# OLED_Display.net
KiCad netlist of a schematic drawn in EAGLE
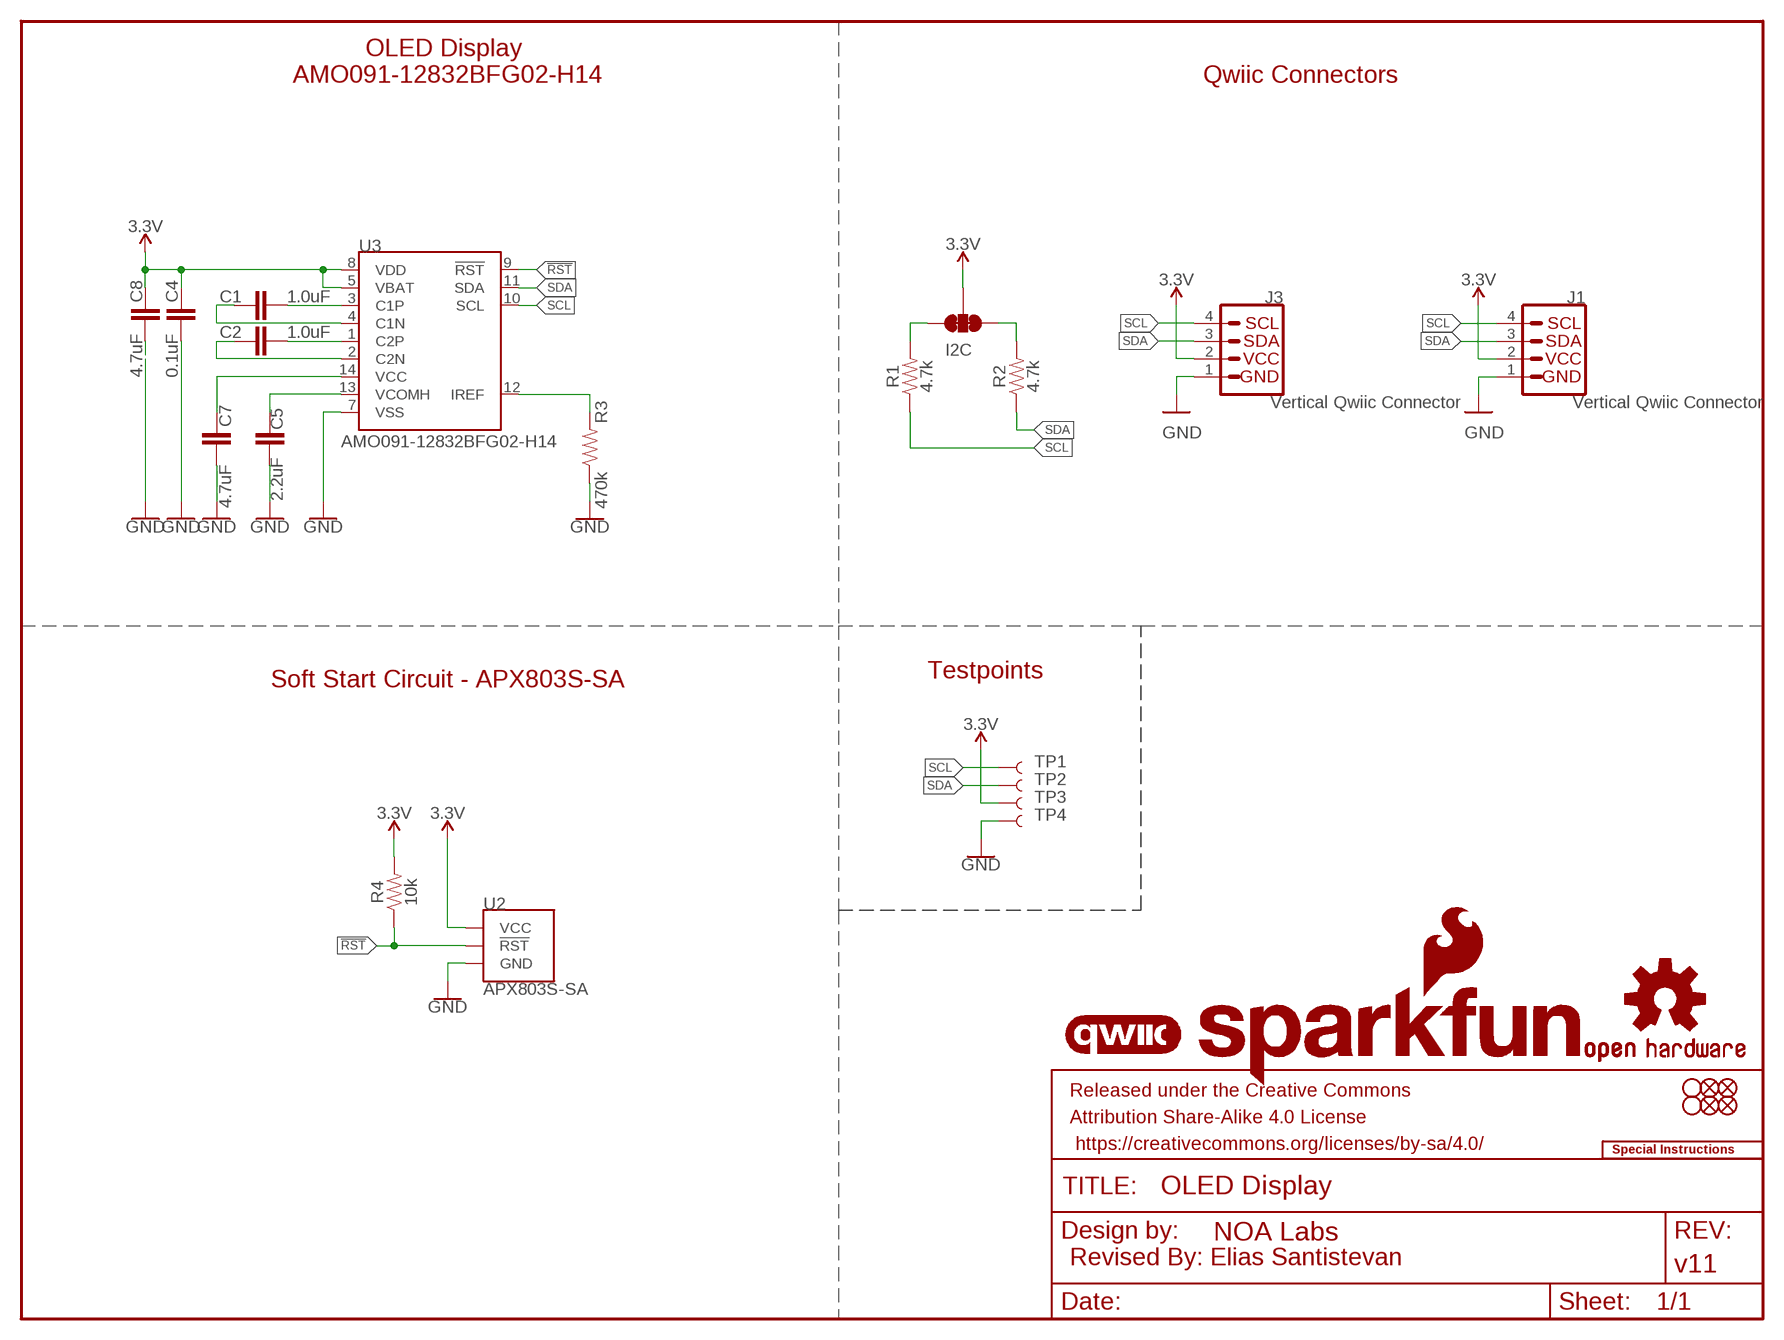
[diagram p0: schematic, sheet 1]

(export (version "E")
  (design (tool "Eeschema 10.0.6"))
  (components
    (comp (ref "C1")
      (value "1.0uF")
      (footprint "eagle-import:0603")
      (libsource (lib "eagle-import") (part "1.0UF-0603-16V-10%"))
    )
    (comp (ref "C2")
      (value "1.0uF")
      (footprint "eagle-import:0603")
      (libsource (lib "eagle-import") (part "1.0UF-0603-16V-10%"))
    )
    (comp (ref "C4")
      (value "0.1uF")
      (footprint "eagle-import:0603")
      (libsource (lib "eagle-import") (part "0.1UF-0603-25V-(+80/-20%)"))
    )
    (comp (ref "C5")
      (value "2.2uF")
      (footprint "eagle-import:0603")
      (libsource (lib "eagle-import") (part "2.2UF-0603-10V-20%"))
    )
    (comp (ref "C7")
      (value "4.7uF")
      (footprint "eagle-import:0603")
      (libsource (lib "eagle-import") (part "4.7UF-0603-6.3V-(10%)"))
    )
    (comp (ref "C8")
      (value "4.7uF")
      (footprint "eagle-import:0603")
      (libsource (lib "eagle-import") (part "4.7UF-0603-6.3V-(10%)"))
    )
    (comp (ref "FD1")
      (value "FIDUCIAL1X2")
      (footprint "eagle-import:FIDUCIAL-1X2")
      (libsource (lib "eagle-import") (part "FIDUCIAL1X2"))
    )
    (comp (ref "FD2")
      (value "FIDUCIAL1X2")
      (footprint "eagle-import:FIDUCIAL-1X2")
      (libsource (lib "eagle-import") (part "FIDUCIAL1X2"))
    )
    (comp (ref "FD3")
      (value "FIDUCIAL1X2")
      (footprint "eagle-import:FIDUCIAL-1X2")
      (libsource (lib "eagle-import") (part "FIDUCIAL1X2"))
    )
    (comp (ref "FD4")
      (value "FIDUCIAL1X2")
      (footprint "eagle-import:FIDUCIAL-1X2")
      (libsource (lib "eagle-import") (part "FIDUCIAL1X2"))
    )
    (comp (ref "FRAME2")
      (value "FRAME-LETTER")
      (footprint "eagle-import:CREATIVE_COMMONS")
      (fields (field (name "DESIGNER") "NOA Labs") (field (name "REV") "v11"))
      (libsource (lib "eagle-import") (part "FRAME-LETTER"))
    )
    (comp (ref "H1")
      (value "STAND-OFFTIGHT")
      (footprint "eagle-import:STAND-OFF-TIGHT")
      (libsource (lib "eagle-import") (part "STAND-OFFTIGHT"))
    )
    (comp (ref "H2")
      (value "STAND-OFFTIGHT")
      (footprint "eagle-import:STAND-OFF-TIGHT")
      (libsource (lib "eagle-import") (part "STAND-OFFTIGHT"))
    )
    (comp (ref "I2C")
      (value "JUMPER-SMT_3_2-NC_TRACE_SILK")
      (footprint "eagle-import:SMT-JUMPER_3_2-NC_TRACE_SILK")
      (libsource (lib "eagle-import") (part "JUMPER-SMT_3_2-NC_TRACE_SILK"))
    )
    (comp (ref "J1")
      (value "Vertical Qwiic Connector")
      (footprint "eagle-import:JST04_1MM_VERT")
      (libsource (lib "eagle-import") (part "QWIIC_CONNECTOR"))
    )
    (comp (ref "J3")
      (value "Vertical Qwiic Connector")
      (footprint "eagle-import:JST04_1MM_VERT")
      (libsource (lib "eagle-import") (part "QWIIC_CONNECTOR"))
    )
    (comp (ref "LOGO1")
      (value "SFE_LOGO_NAME_FLAME.1_INCH")
      (footprint "eagle-import:SFE_LOGO_NAME_FLAME_.1")
      (libsource (lib "eagle-import") (part "SFE_LOGO_NAME_FLAME.1_INCH"))
    )
    (comp (ref "LOGO2")
      (value "OSHW-LOGOMINI")
      (footprint "eagle-import:OSHW-LOGO-MINI")
      (libsource (lib "eagle-import") (part "OSHW-LOGOMINI"))
    )
    (comp (ref "LOGO3")
      (value "QWIIC_LOGO_4MM")
      (footprint "eagle-import:QWIIC_4MM")
      (libsource (lib "eagle-import") (part "QWIIC_LOGO_4MM"))
    )
    (comp (ref "LOGO4")
      (value "SPECIAL_INSTRUCTIONS-ORDERING")
      (footprint "eagle-import:ORDERING_INSTRUCTIONS")
      (libsource (lib "eagle-import") (part "SPECIAL_INSTRUCTIONS-ORDERING"))
    )
    (comp (ref "R1")
      (value "4.7k")
      (footprint "eagle-import:0603")
      (libsource (lib "eagle-import") (part "4.7KOHM-0603-1/10W-1%"))
    )
    (comp (ref "R2")
      (value "4.7k")
      (footprint "eagle-import:0603")
      (libsource (lib "eagle-import") (part "4.7KOHM-0603-1/10W-1%"))
    )
    (comp (ref "R3")
      (value "470k")
      (footprint "eagle-import:0603")
      (libsource (lib "eagle-import") (part "470KOHM"))
    )
    (comp (ref "R4")
      (value "10k")
      (footprint "eagle-import:0603")
      (libsource (lib "eagle-import") (part "10KOHM-0603-1/10W-1%"))
    )
    (comp (ref "TP1")
      (value "TEST-POINT3X4")
      (footprint "eagle-import:PAD.03X.04")
      (libsource (lib "eagle-import") (part "TEST-POINT3X4"))
    )
    (comp (ref "TP2")
      (value "TEST-POINT3X4")
      (footprint "eagle-import:PAD.03X.04")
      (libsource (lib "eagle-import") (part "TEST-POINT3X4"))
    )
    (comp (ref "TP3")
      (value "TEST-POINT3X4")
      (footprint "eagle-import:PAD.03X.04")
      (libsource (lib "eagle-import") (part "TEST-POINT3X4"))
    )
    (comp (ref "TP4")
      (value "TEST-POINT3X4")
      (footprint "eagle-import:PAD.03X.04")
      (libsource (lib "eagle-import") (part "TEST-POINT3X4"))
    )
    (comp (ref "U2")
      (value "APX803S-SA")
      (footprint "eagle-import:SOT23-3")
      (libsource (lib "eagle-import") (part "APX803S-SA"))
    )
    (comp (ref "U3")
      (value "AMO091-12832BFG02-H14")
      (footprint "eagle-import:AMO091-12832BFG02-H14")
      (libsource (lib "eagle-import") (part "AMO091-12832BFG02-H14"))
    )
  )
  (nets
    (net (code "1") (name "/~{RST}") (class "Default")
      (node (ref "R4") (pin "1") (pinfunction "1_1") (pintype "passive"))
      (node (ref "U2") (pin "2") (pinfunction "~{RST}_2") (pintype "bidirectional"))
      (node (ref "U3") (pin "9") (pinfunction "~{RST}_9") (pintype "bidirectional"))
    )
    (net (code "2") (name "3.3V") (class "Default")
      (node (ref "C4") (pin "1") (pinfunction "1_1") (pintype "passive"))
      (node (ref "C8") (pin "2") (pinfunction "2_2") (pintype "passive"))
      (node (ref "I2C") (pin "2") (pinfunction "2_2") (pintype "passive"))
      (node (ref "J1") (pin "2") (pinfunction "2_2") (pintype "power_in"))
      (node (ref "J3") (pin "2") (pinfunction "2_2") (pintype "power_in"))
      (node (ref "R4") (pin "2") (pinfunction "2_2") (pintype "passive"))
      (node (ref "TP3") (pin "1") (pinfunction "1_1") (pintype "bidirectional"))
      (node (ref "U2") (pin "3") (pinfunction "VCC_3") (pintype "bidirectional"))
      (node (ref "U3") (pin "5") (pinfunction "VBAT_5") (pintype "bidirectional"))
      (node (ref "U3") (pin "8") (pinfunction "VDD_8") (pintype "bidirectional"))
    )
    (net (code "3") (name "GND") (class "Default")
      (node (ref "C4") (pin "2") (pinfunction "2_2") (pintype "passive"))
      (node (ref "C5") (pin "2") (pinfunction "2_2") (pintype "passive"))
      (node (ref "C7") (pin "1") (pinfunction "1_1") (pintype "passive"))
      (node (ref "C8") (pin "1") (pinfunction "1_1") (pintype "passive"))
      (node (ref "J1") (pin "1") (pinfunction "1_1") (pintype "power_in"))
      (node (ref "J3") (pin "1") (pinfunction "1_1") (pintype "power_in"))
      (node (ref "R3") (pin "1") (pinfunction "1_1") (pintype "passive"))
      (node (ref "TP4") (pin "1") (pinfunction "1_1") (pintype "bidirectional"))
      (node (ref "U2") (pin "1") (pinfunction "GND_1") (pintype "bidirectional"))
      (node (ref "U3") (pin "7") (pinfunction "VSS_7") (pintype "bidirectional"))
    )
    (net (code "4") (name "Net-(I2C-Pad1)") (class "Default")
      (node (ref "I2C") (pin "1") (pinfunction "1_1") (pintype "passive"))
      (node (ref "R2") (pin "2") (pinfunction "2_2") (pintype "passive"))
    )
    (net (code "5") (name "Net-(I2C-Pad3)") (class "Default")
      (node (ref "I2C") (pin "3") (pinfunction "3_3") (pintype "passive"))
      (node (ref "R1") (pin "2") (pinfunction "2_2") (pintype "passive"))
    )
    (net (code "6") (name "Net-(U3-C1N)") (class "Default")
      (node (ref "C1") (pin "1") (pinfunction "1_1") (pintype "passive"))
      (node (ref "U3") (pin "4") (pinfunction "C1N_4") (pintype "bidirectional"))
    )
    (net (code "7") (name "Net-(U3-C1P)") (class "Default")
      (node (ref "C1") (pin "2") (pinfunction "2_2") (pintype "passive"))
      (node (ref "U3") (pin "3") (pinfunction "C1P_3") (pintype "bidirectional"))
    )
    (net (code "8") (name "Net-(U3-C2N)") (class "Default")
      (node (ref "C2") (pin "1") (pinfunction "1_1") (pintype "passive"))
      (node (ref "U3") (pin "2") (pinfunction "C2N_2") (pintype "bidirectional"))
    )
    (net (code "9") (name "Net-(U3-C2P)") (class "Default")
      (node (ref "C2") (pin "2") (pinfunction "2_2") (pintype "passive"))
      (node (ref "U3") (pin "1") (pinfunction "C2P_1") (pintype "bidirectional"))
    )
    (net (code "10") (name "Net-(U3-IREF)") (class "Default")
      (node (ref "R3") (pin "2") (pinfunction "2_2") (pintype "passive"))
      (node (ref "U3") (pin "12") (pinfunction "IREF_12") (pintype "bidirectional"))
    )
    (net (code "11") (name "Net-(U3-VCC)") (class "Default")
      (node (ref "C7") (pin "2") (pinfunction "2_2") (pintype "passive"))
      (node (ref "U3") (pin "14") (pinfunction "VCC_14") (pintype "bidirectional"))
    )
    (net (code "12") (name "Net-(U3-VCOMH)") (class "Default")
      (node (ref "C5") (pin "1") (pinfunction "1_1") (pintype "passive"))
      (node (ref "U3") (pin "13") (pinfunction "VCOMH_13") (pintype "bidirectional"))
    )
    (net (code "13") (name "SCL") (class "Default")
      (node (ref "J1") (pin "4") (pinfunction "4_4") (pintype "passive"))
      (node (ref "J3") (pin "4") (pinfunction "4_4") (pintype "passive"))
      (node (ref "R1") (pin "1") (pinfunction "1_1") (pintype "passive"))
      (node (ref "TP1") (pin "1") (pinfunction "1_1") (pintype "bidirectional"))
      (node (ref "U3") (pin "10") (pinfunction "SCL_10") (pintype "bidirectional"))
    )
    (net (code "14") (name "SDA") (class "Default")
      (node (ref "J1") (pin "3") (pinfunction "3_3") (pintype "passive"))
      (node (ref "J3") (pin "3") (pinfunction "3_3") (pintype "passive"))
      (node (ref "R2") (pin "1") (pinfunction "1_1") (pintype "passive"))
      (node (ref "TP2") (pin "1") (pinfunction "1_1") (pintype "bidirectional"))
      (node (ref "U3") (pin "11") (pinfunction "SDA_11") (pintype "bidirectional"))
    )
  )
)
